# Power_Supply.net
KiCad netlist of a schematic drawn in Altium Designer
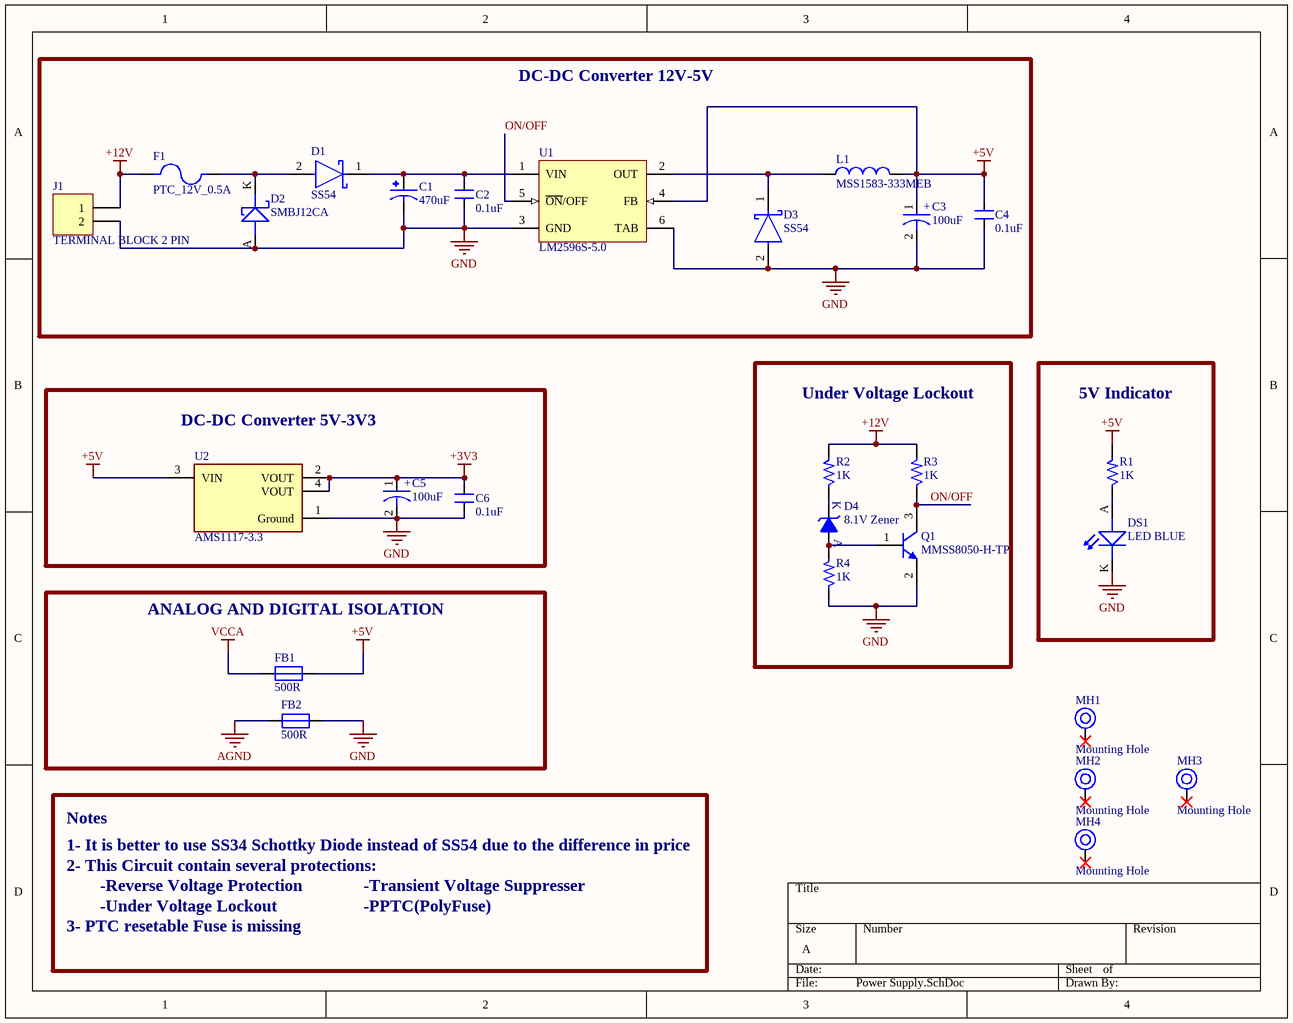
[diagram p0: Power Supply.SchDoc]

(export (version "E")
  (design (tool "Eeschema 10.0.6"))
  (components
    (comp (ref "C1")
      (value "470uF")
      (footprint "CAPPRD500W50D630H1120")
      (description "100F 25V Aluminum Electrolytic Capacitors Radial, Can 1000 Hrs @ 105C")
      (fields (field (name "MF") "Panasonic") (field (name "MP") "EEU-FC1E101SB"))
      (libsource (lib "TAREKPCBLIB") (part "CAP_100uF_25V_TH"))
    )
    (comp (ref "C2")
      (value "0.1uF")
      (footprint "CAP_0805")
      (description "0.1µF ±20% 50V Ceramic Capacitor X7R 0805 (2012 Metric)")
      (fields
        (field (name "MANUFACTURER") "Samsung Electro-Mechanics")
        (field (name "MANUFACTURER PART NUMBER") "CL21B104MBCNNNC")
      )
      (libsource (lib "ESTEEMPCBLIB") (part "CAP_0.1uF-50V-20%-0805"))
    )
    (comp (ref "C3")
      (value "100uF")
      (footprint "ACAP_P305_D393_H393_RAD")
      (description "100µF 50V Aluminum Polymer Capacitor Radial, Can - SMD 28mOhm 4000 Hrs @ 125°C")
      (fields
        (field (name "MANUFACTURER") "Nichicon")
        (field (name "MANUFACTURER PART NUMBER") "GYA1H101MCQ1GS")
      )
      (libsource (lib "ESTEEMPCBLIB") (part "CAP-P_100uF-50V-20%-RAD"))
    )
    (comp (ref "C4")
      (value "0.1uF")
      (footprint "CAP_0805")
      (description "0.1µF ±20% 50V Ceramic Capacitor X7R 0805 (2012 Metric)")
      (fields
        (field (name "MANUFACTURER") "Samsung Electro-Mechanics")
        (field (name "MANUFACTURER PART NUMBER") "CL21B104MBCNNNC")
      )
      (libsource (lib "ESTEEMPCBLIB") (part "CAP_0.1uF-50V-20%-0805"))
    )
    (comp (ref "C5")
      (value "100uF")
      (footprint "ACAP_P236_D305_H303_RAD")
      (description "100µF 25V Aluminum Electrolytic Capacitors Radial, Can - SMD 1000 Hrs @ 105°C")
      (fields
        (field (name "MANUFACTURER") "Nichicon")
        (field (name "MANUFACTURER PART NUMBER") "UWT1E101MCL1GS")
      )
      (libsource (lib "ESTEEMPCBLIB") (part "CAP-P_100uF-25V-20%-RAD"))
    )
    (comp (ref "C6")
      (value "0.1uF")
      (footprint "CAP_0805")
      (description "0.1µF ±20% 50V Ceramic Capacitor X7R 0805 (2012 Metric)")
      (fields
        (field (name "MANUFACTURER") "Samsung Electro-Mechanics")
        (field (name "MANUFACTURER PART NUMBER") "CL21B104MBCNNNC")
      )
      (libsource (lib "ESTEEMPCBLIB") (part "CAP_0.1uF-50V-20%-0805"))
    )
    (comp (ref "D1")
      (value "SS54")
      (footprint "FP-95400-MFG")
      (description "DIODE SCHOTTKY 40V 5A DO214AC")
      (libsource (lib "TAREKPCBLIB") (part "SS54-Schottky-40V-3A-DO214AC"))
    )
    (comp (ref "D2")
      (value "SMBJ12CA")
      (footprint "DIO_SMB_DO-214AA")
      (description "19.9V Clamp 30.2A Ipp Tvs Diode Surface Mount DO-214AA (SMBJ)")
      (fields (field (name "MANUFACTURER") "Texas Instruments"))
      (libsource (lib "ESTEEMPCBLIB") (part "DIO-T_12V-19.9V-30A-DO214AA"))
    )
    (comp (ref "D3")
      (value "SS54")
      (footprint "FP-95400-MFG")
      (description "DIODE SCHOTTKY 40V 5A DO214AC")
      (libsource (lib "TAREKPCBLIB") (part "SS54-Schottky-40V-3A-DO214AC"))
    )
    (comp (ref "D4")
      (value "8.1V Zener")
      (footprint "DIO_SOD80C")
      (description "Zener Diode 8.2V 500mW Surface Mount SOD-80 MiniMELF")
      (fields
        (field (name "MANUFACTURER") "Microsemi")
        (field (name "MANUFACTURER PART NUMBER") "TZMA8V2-GS08")
      )
      (libsource (lib "ESTEEMPCBLIB") (part "DIO-Z_8.1V-500mW-SOD-80"))
    )
    (comp (ref "DS1")
      (value "LED BLUE")
      (footprint "LED_0805")
      (description "Blue 470nm LED Indication - Discrete 3.3V 0805 (2012 Metric)")
      (fields
        (field (name "MANUFACTURER") "Vishay Lite-On")
        (field (name "MANUFACTURER PART NUMBER") "LTST-C171TBKT")
      )
      (libsource (lib "ESTEEMPCBLIB") (part "LED_BLUE-3V3-20mA-0805"))
    )
    (comp (ref "F1")
      (value "PTC_12V_0.5A")
      (footprint "FUSER_MF-MSMF200")
      (description "MF-MSMF200_Polymeric PTC Resettable Fuse 8V 2A Ih Surface Mount 1812 (4532 Metric), Concave")
      (fields (field (name "MP") "MF-MSMF200") (field (name "MF") "Bourns"))
      (libsource (lib "TAREKPCBLIB") (part "PTC_8V_2A_SMD_1812"))
    )
    (comp (ref "FB1")
      (value "500R")
      (footprint "IND_0805")
      (description "500 Ohms @ 100MHz 1 Ferrite Bead 0805 (2012 Metric) 500mA 300mOhm")
      (fields
        (field (name "MANUFACTURER") "Abracon")
        (field (name "MANUFACTURER PART NUMBER") "ACML-0805-501-T")
      )
      (libsource (lib "ESTEEMPCBLIB") (part "FB_500R-100Mhz-500mA-0805"))
    )
    (comp (ref "FB2")
      (value "500R")
      (footprint "IND_0805")
      (description "500 Ohms @ 100MHz 1 Ferrite Bead 0805 (2012 Metric) 500mA 300mOhm")
      (fields
        (field (name "MANUFACTURER") "Abracon")
        (field (name "MANUFACTURER PART NUMBER") "ACML-0805-501-T")
      )
      (libsource (lib "ESTEEMPCBLIB") (part "FB_500R-100Mhz-500mA-0805"))
    )
    (comp (ref "J1")
      (value "TERMINAL BLOCK 2 PIN")
      (footprint "CON2_P196_1729128_TH_ST")
      (description "2 Pins, 1 Row 5mm Pitch, straight Connector, male")
      (fields
        (field (name "MANUFACTURER") "Phoenix Contact")
        (field (name "MANUFACTURER PART NUMBER") "MKDSN1,5/2")
      )
      (libsource (lib "ESTEEMPCBLIB") (part "CON-TB_2X1-196-ST-TH"))
    )
    (comp (ref "L1")
      (value "MSS1583-333MEB")
      (footprint "IND_456_640_236X117_SMD")
      (description "Fixed Inductors MSS1583 SMT Power 0.038Ohms 33uH")
      (fields (field (name "MANUFACTURER") "Coilcraft"))
      (libsource (lib "ESTEEMPCBLIB") (part "IND_33uH-8A-20%-SMD"))
    )
    (comp (ref "MH1")
      (value "Mounting Hole")
      (footprint "MOUNTING")
      (fields (field (name "MANUFACTURER PART NUMBER") "NA"))
      (libsource (lib "ESTEEMPCBLIB") (part "MH_3.5H_6D"))
    )
    (comp (ref "MH2")
      (value "Mounting Hole")
      (footprint "MOUNTING")
      (fields (field (name "MANUFACTURER PART NUMBER") "NA"))
      (libsource (lib "ESTEEMPCBLIB") (part "MH_3.5H_6D"))
    )
    (comp (ref "MH3")
      (value "Mounting Hole")
      (footprint "MOUNTING")
      (fields (field (name "MANUFACTURER PART NUMBER") "NA"))
      (libsource (lib "ESTEEMPCBLIB") (part "MH_3.5H_6D"))
    )
    (comp (ref "MH4")
      (value "Mounting Hole")
      (footprint "MOUNTING")
      (fields (field (name "MANUFACTURER PART NUMBER") "NA"))
      (libsource (lib "ESTEEMPCBLIB") (part "MH_3.5H_6D"))
    )
    (comp (ref "Q1")
      (value "MMSS8050-H-TP")
      (footprint "SOT 23-3")
      (description "Bipolar (BJT) Transistor NPN 25V 1.5A 100MHz 625mW Surface Mount SOT-23")
      (fields (field (name "MANUFACTURER") "MCC"))
      (libsource (lib "ESTEEMPCBLIB") (part "TRNS-NPN_25V-1.5A-SOT23"))
    )
    (comp (ref "R1")
      (value "1K")
      (footprint "RES_0805")
      (description "1 kOhms ±1% 0.125W, 1/8W Chip Resistor 0805 (2012 Metric) Moisture Resistant Thick Film")
      (fields (field (name "MANUFACTURER") "Walsin") (field (name "MANUFACTURER PART NUMBER") "WR08X1001FTL"))
      (libsource (lib "ESTEEMPCBLIB") (part "RES_1K-0.125W-1%-0805"))
    )
    (comp (ref "R2")
      (value "1K")
      (footprint "RES_0805")
      (description "1 kOhms ±1% 0.125W, 1/8W Chip Resistor 0805 (2012 Metric) Moisture Resistant Thick Film")
      (fields (field (name "MANUFACTURER") "Walsin") (field (name "MANUFACTURER PART NUMBER") "WR08X1001FTL"))
      (libsource (lib "ESTEEMPCBLIB") (part "RES_1K-0.125W-1%-0805"))
    )
    (comp (ref "R3")
      (value "1K")
      (footprint "RES_0805")
      (description "1 kOhms ±1% 0.125W, 1/8W Chip Resistor 0805 (2012 Metric) Moisture Resistant Thick Film")
      (fields (field (name "MANUFACTURER") "Walsin") (field (name "MANUFACTURER PART NUMBER") "WR08X1001FTL"))
      (libsource (lib "ESTEEMPCBLIB") (part "RES_1K-0.125W-1%-0805"))
    )
    (comp (ref "R4")
      (value "1K")
      (footprint "RES_0805")
      (description "1 kOhms ±1% 0.125W, 1/8W Chip Resistor 0805 (2012 Metric) Moisture Resistant Thick Film")
      (fields (field (name "MANUFACTURER") "Walsin") (field (name "MANUFACTURER PART NUMBER") "WR08X1001FTL"))
      (libsource (lib "ESTEEMPCBLIB") (part "RES_1K-0.125W-1%-0805"))
    )
    (comp (ref "U1")
      (value "LM2596S-5.0")
      (footprint "TO170P1524X483-6N")
      (description "SIMPLE SWITCHER® Power Converter 150 KHz 3A Step-Down Voltage Regulator, 5-pin TO-263, Pb-Free")
      (fields (field (name "MANUFACTURER") "Texas Instruments"))
      (libsource (lib "TAREKPCBLIB") (part "LM2596S-5.0/SMPS"))
    )
    (comp (ref "U2")
      (value "AMS1117-3.3")
      (footprint "FP-AMS1117-IPC_A")
      (description "LDO Voltage Regulators 1A, 3.3V")
      (fields
        (field (name "OCTOPART") "https://octopart.com/ams1117-3.3-advanced+monolithic+systems-25899300")
        (field (name "MANUFACTURER") "Advanced Monolithic Systems")
      )
      (libsource (lib "TAREKPCBLIB") (part "AMS1117-3.3/LDO"))
    )
  )
  (nets
    (net (code "1") (name "+3V3") (class "Default")
      (node (ref "C5") (pin "1") (pinfunction "1_1") (pintype "passive"))
      (node (ref "C6") (pin "2") (pinfunction "2_2") (pintype "passive"))
      (node (ref "U2") (pin "2") (pinfunction "VOUT_2") (pintype "passive"))
      (node (ref "U2") (pin "4") (pinfunction "VOUT_4") (pintype "passive"))
    )
    (net (code "2") (name "+5V") (class "Default")
      (node (ref "C3") (pin "1") (pinfunction "1_1") (pintype "passive"))
      (node (ref "C4") (pin "2") (pinfunction "2_2") (pintype "passive"))
      (node (ref "FB1") (pin "2") (pinfunction "2_2") (pintype "passive"))
      (node (ref "L1") (pin "2") (pinfunction "2_2") (pintype "passive"))
      (node (ref "R1") (pin "2") (pinfunction "2_2") (pintype "passive"))
      (node (ref "U1") (pin "4") (pinfunction "FB_4") (pintype "input"))
      (node (ref "U2") (pin "3") (pinfunction "VIN_3") (pintype "power_in"))
    )
    (net (code "3") (name "+12V") (class "Default")
      (node (ref "F1") (pin "1") (pinfunction "1_1") (pintype "passive"))
      (node (ref "J1") (pin "1") (pinfunction "1_1") (pintype "passive"))
      (node (ref "R2") (pin "2") (pinfunction "2_2") (pintype "passive"))
      (node (ref "R3") (pin "2") (pinfunction "2_2") (pintype "passive"))
    )
    (net (code "4") (name "/ON{slash}OFF") (class "Default")
      (node (ref "Q1") (pin "3") (pinfunction "C_3") (pintype "passive"))
      (node (ref "R3") (pin "1") (pinfunction "1_1") (pintype "passive"))
      (node (ref "U1") (pin "5") (pinfunction "~{ON}/OFF_5") (pintype "input"))
    )
    (net (code "5") (name "AGND") (class "Default")
      (node (ref "FB2") (pin "1") (pinfunction "1_1") (pintype "passive"))
    )
    (net (code "6") (name "GND") (class "Default")
      (node (ref "C1") (pin "N") (pinfunction "N_N") (pintype "passive"))
      (node (ref "C2") (pin "1") (pinfunction "1_1") (pintype "passive"))
      (node (ref "C3") (pin "2") (pinfunction "2_2") (pintype "passive"))
      (node (ref "C4") (pin "1") (pinfunction "1_1") (pintype "passive"))
      (node (ref "C5") (pin "2") (pinfunction "2_2") (pintype "passive"))
      (node (ref "C6") (pin "1") (pinfunction "1_1") (pintype "passive"))
      (node (ref "D2") (pin "A") (pinfunction "A_A") (pintype "passive"))
      (node (ref "D3") (pin "2") (pinfunction "A_2") (pintype "passive"))
      (node (ref "DS1") (pin "K") (pinfunction "CATHODE_K") (pintype "passive"))
      (node (ref "FB2") (pin "2") (pinfunction "2_2") (pintype "passive"))
      (node (ref "J1") (pin "2") (pinfunction "2_2") (pintype "passive"))
      (node (ref "Q1") (pin "2") (pinfunction "E_2") (pintype "passive"))
      (node (ref "R4") (pin "1") (pinfunction "1_1") (pintype "passive"))
      (node (ref "U1") (pin "3") (pinfunction "GND_3") (pintype "power_in"))
      (node (ref "U1") (pin "6") (pinfunction "TAB_6") (pintype "power_in"))
      (node (ref "U2") (pin "1") (pinfunction "Ground_1") (pintype "power_in"))
    )
    (net (code "7") (name "Net-(D1-A)") (class "Default")
      (node (ref "D1") (pin "2") (pinfunction "A_2") (pintype "passive"))
      (node (ref "D2") (pin "K") (pinfunction "K_K") (pintype "passive"))
      (node (ref "F1") (pin "2") (pinfunction "2_2") (pintype "passive"))
    )
    (net (code "8") (name "Net-(D1-C)") (class "Default")
      (node (ref "C1") (pin "P") (pinfunction "P_P") (pintype "passive"))
      (node (ref "C2") (pin "2") (pinfunction "2_2") (pintype "passive"))
      (node (ref "D1") (pin "1") (pinfunction "C_1") (pintype "passive"))
      (node (ref "U1") (pin "1") (pinfunction "VIN_1") (pintype "power_in"))
    )
    (net (code "9") (name "Net-(D3-C)") (class "Default")
      (node (ref "D3") (pin "1") (pinfunction "C_1") (pintype "passive"))
      (node (ref "L1") (pin "1") (pinfunction "1_1") (pintype "passive"))
      (node (ref "U1") (pin "2") (pinfunction "OUT_2") (pintype "power_in"))
    )
    (net (code "10") (name "Net-(D4-PadK)") (class "Default")
      (node (ref "D4") (pin "K") (pinfunction "K_K") (pintype "passive"))
      (node (ref "R2") (pin "1") (pinfunction "1_1") (pintype "passive"))
    )
    (net (code "11") (name "Net-(DS1-ANODE)") (class "Default")
      (node (ref "DS1") (pin "A") (pinfunction "ANODE_A") (pintype "passive"))
      (node (ref "R1") (pin "1") (pinfunction "1_1") (pintype "passive"))
    )
    (net (code "12") (name "Net-(Q1-B)") (class "Default")
      (node (ref "D4") (pin "A") (pinfunction "A_A") (pintype "passive"))
      (node (ref "Q1") (pin "1") (pinfunction "B_1") (pintype "passive"))
      (node (ref "R4") (pin "2") (pinfunction "2_2") (pintype "passive"))
    )
    (net (code "13") (name "VCCA") (class "Default")
      (node (ref "FB1") (pin "1") (pinfunction "1_1") (pintype "passive"))
    )
    (net (code "14") (name "unconnected-(MH1-Pad1)") (class "Default")
      (node (ref "MH1") (pin "1") (pinfunction "1_1") (pintype "passive+no_connect"))
    )
    (net (code "15") (name "unconnected-(MH2-Pad1)") (class "Default")
      (node (ref "MH2") (pin "1") (pinfunction "1_1") (pintype "passive+no_connect"))
    )
    (net (code "16") (name "unconnected-(MH3-Pad1)") (class "Default")
      (node (ref "MH3") (pin "1") (pinfunction "1_1") (pintype "passive+no_connect"))
    )
    (net (code "17") (name "unconnected-(MH4-Pad1)") (class "Default")
      (node (ref "MH4") (pin "1") (pinfunction "1_1") (pintype "passive+no_connect"))
    )
  )
)
